# General_Overview.net
KiCad netlist of a schematic drawn in Altium Designer
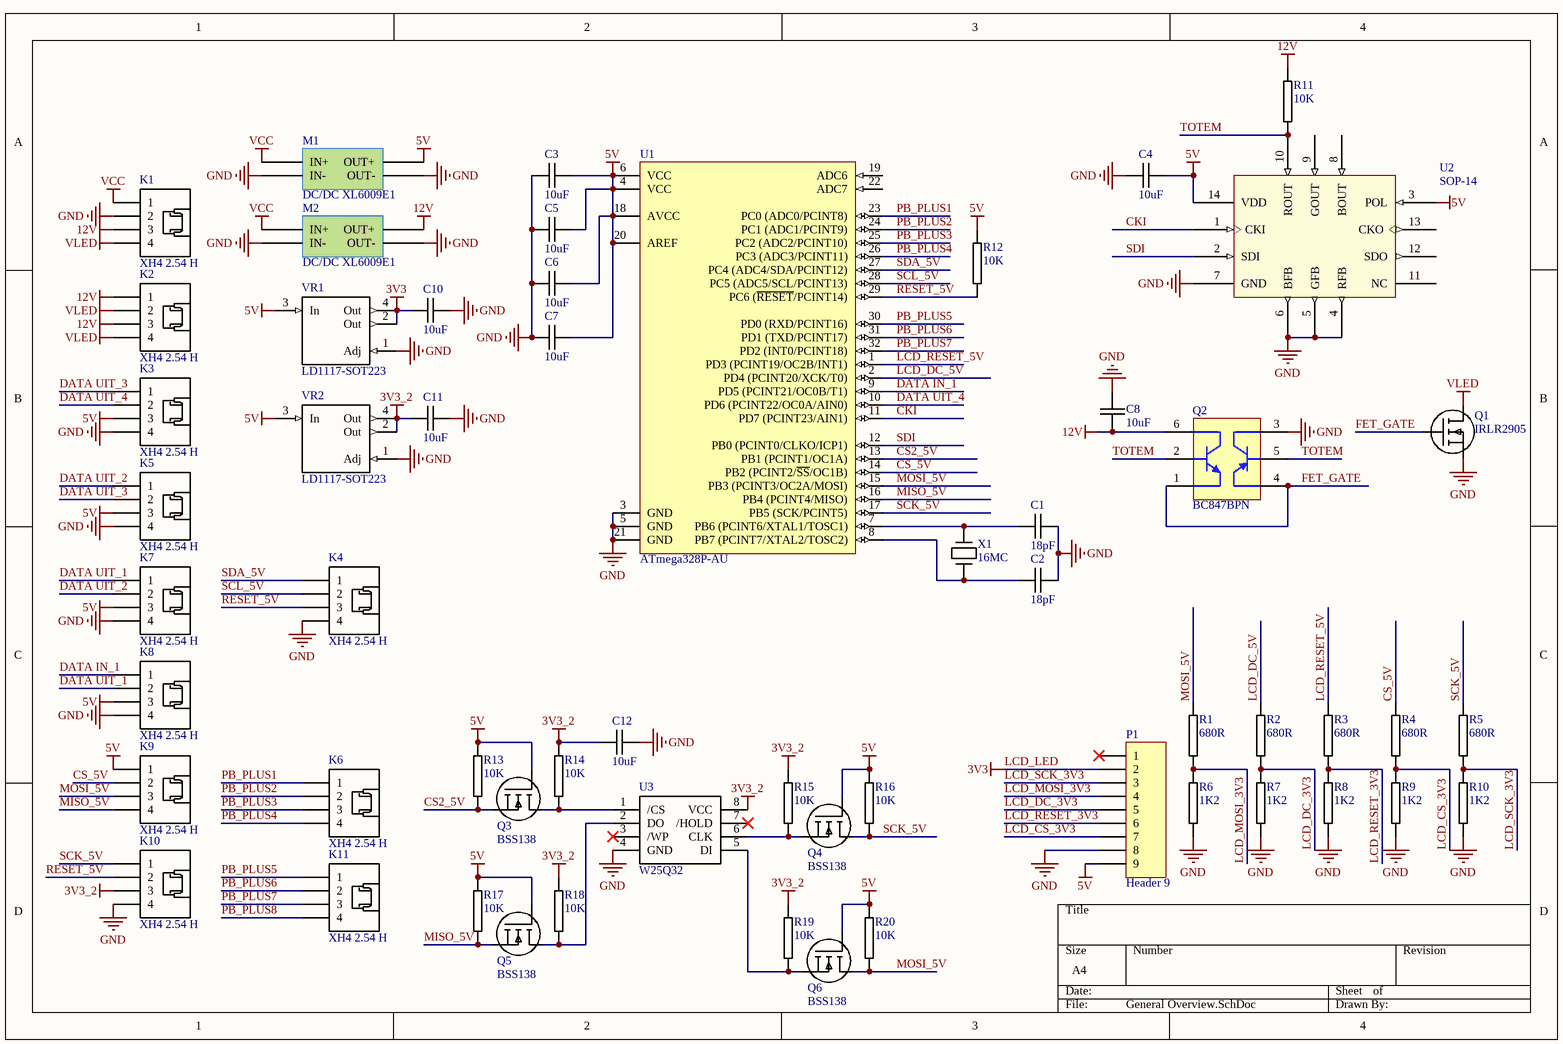
[diagram p0: General Overview.SchDoc]

(export (version "E")
  (design (tool "Eeschema 10.0.6"))
  (components
    (comp (ref "C1")
      (value "18pF")
      (footprint "0603C-GENERIC")
      (description "CAPACITOR 0603 CERAMIC")
      (libsource (lib "SMD Capacitors 0603") (part "0603C-15PF-50V-C0G-MUR"))
    )
    (comp (ref "C2")
      (value "18pF")
      (footprint "0603C-GENERIC")
      (description "CAPACITOR 0603 CERAMIC")
      (libsource (lib "SMD Capacitors 0603") (part "0603C-15PF-50V-C0G-MUR"))
    )
    (comp (ref "C3")
      (value "10uF")
      (footprint "0805C-GENERIC")
      (description "CAPACITOR 0805 CERAMIC")
      (libsource (lib "SMD Capacitors 0805") (part "0805C-10UF-25V-X5R-SAM"))
    )
    (comp (ref "C4")
      (value "10uF")
      (footprint "0805C-GENERIC")
      (description "CAPACITOR 0805 CERAMIC")
      (libsource (lib "SMD Capacitors 0805") (part "0805C-10UF-25V-X5R-SAM"))
    )
    (comp (ref "C5")
      (value "10uF")
      (footprint "0805C-GENERIC")
      (description "CAPACITOR 0805 CERAMIC")
      (libsource (lib "SMD Capacitors 0805") (part "0805C-10UF-25V-X5R-SAM"))
    )
    (comp (ref "C6")
      (value "10uF")
      (footprint "0805C-GENERIC")
      (description "CAPACITOR 0805 CERAMIC")
      (libsource (lib "SMD Capacitors 0805") (part "0805C-10UF-25V-X5R-SAM"))
    )
    (comp (ref "C7")
      (value "10uF")
      (footprint "0805C-GENERIC")
      (description "CAPACITOR 0805 CERAMIC")
      (libsource (lib "SMD Capacitors 0805") (part "0805C-10UF-25V-X5R-SAM"))
    )
    (comp (ref "C8")
      (value "10uF")
      (footprint "0805C-GENERIC")
      (description "CAPACITOR 0805 CERAMIC")
      (libsource (lib "SMD Capacitors 0805") (part "0805C-10UF-25V-X5R-SAM"))
    )
    (comp (ref "C10")
      (value "10uF")
      (footprint "0805C-GENERIC")
      (description "CAPACITOR 0805 CERAMIC")
      (libsource (lib "SMD Capacitors 0805") (part "0805C-10UF-25V-X5R-SAM"))
    )
    (comp (ref "C11")
      (value "10uF")
      (footprint "0805C-GENERIC")
      (description "CAPACITOR 0805 CERAMIC")
      (libsource (lib "SMD Capacitors 0805") (part "0805C-10UF-25V-X5R-SAM"))
    )
    (comp (ref "C12")
      (value "10uF")
      (footprint "0805C-GENERIC")
      (description "CAPACITOR 0805 CERAMIC")
      (libsource (lib "SMD Capacitors 0805") (part "0805C-10UF-25V-X5R-SAM"))
    )
    (comp (ref "K1")
      (value "XH4 2.54 H")
      (footprint "XH4 2.54 H")
      (description "4 PIN XH 2.54")
      (libsource (lib "TH Connectors") (part "XH4 2.54 H"))
    )
    (comp (ref "K2")
      (value "XH4 2.54 H")
      (footprint "XH4 2.54 H")
      (description "4 PIN XH 2.54")
      (libsource (lib "TH Connectors") (part "XH4 2.54 H"))
    )
    (comp (ref "K3")
      (value "XH4 2.54 H")
      (footprint "XH4 2.54 H")
      (description "4 PIN XH 2.54")
      (libsource (lib "TH Connectors") (part "XH4 2.54 H"))
    )
    (comp (ref "K4")
      (value "XH4 2.54 H")
      (footprint "XH4 2.54 H")
      (description "4 PIN XH 2.54")
      (libsource (lib "TH Connectors") (part "XH4 2.54 H"))
    )
    (comp (ref "K5")
      (value "XH4 2.54 H")
      (footprint "XH4 2.54 H")
      (description "4 PIN XH 2.54")
      (libsource (lib "TH Connectors") (part "XH4 2.54 H"))
    )
    (comp (ref "K6")
      (value "XH4 2.54 H")
      (footprint "XH4 2.54 H")
      (description "4 PIN XH 2.54")
      (libsource (lib "TH Connectors") (part "XH4 2.54 H"))
    )
    (comp (ref "K7")
      (value "XH4 2.54 H")
      (footprint "XH4 2.54 H")
      (description "4 PIN XH 2.54")
      (libsource (lib "TH Connectors") (part "XH4 2.54 H"))
    )
    (comp (ref "K8")
      (value "XH4 2.54 H")
      (footprint "XH4 2.54 H")
      (description "4 PIN XH 2.54")
      (libsource (lib "TH Connectors") (part "XH4 2.54 H"))
    )
    (comp (ref "K9")
      (value "XH4 2.54 H")
      (footprint "XH4 2.54 H")
      (description "4 PIN XH 2.54")
      (libsource (lib "TH Connectors") (part "XH4 2.54 H"))
    )
    (comp (ref "K10")
      (value "XH4 2.54 H")
      (footprint "XH4 2.54 H")
      (description "4 PIN XH 2.54")
      (libsource (lib "TH Connectors") (part "XH4 2.54 H"))
    )
    (comp (ref "K11")
      (value "XH4 2.54 H")
      (footprint "XH4 2.54 H")
      (description "4 PIN XH 2.54")
      (libsource (lib "TH Connectors") (part "XH4 2.54 H"))
    )
    (comp (ref "M1")
      (value "DC/DC XL6009E1")
      (footprint "DCDC XL6009E1")
      (libsource (lib "Modules") (part "DC/DC XL6009E1"))
    )
    (comp (ref "M2")
      (value "DC/DC XL6009E1")
      (footprint "DCDC XL6009E1")
      (libsource (lib "Modules") (part "DC/DC XL6009E1"))
    )
    (comp (ref "P1")
      (value "Header 9")
      (footprint "HDR1X9")
      (description "Header, 9-Pin")
      (fields (field (name "PUBLISHER") "Altium Limited"))
      (libsource (lib "Miscellaneous Connectors") (part "Header 9"))
    )
    (comp (ref "Q1")
      (value "IRLR2905")
      (footprint "TO252AA-GDS")
      (description "N CHANNEL MOSFET")
      (libsource (lib "SMD Transistors") (part "IRLR2905"))
    )
    (comp (ref "Q2")
      (value "BC847BPN")
      (footprint "SOT363_N")
      (description "NPN/PNP General-purpose Transistors")
      (fields (field (name "PUBLISHER") "Altium Limited"))
      (libsource (lib "Philips Discrete BJT - Low Power") (part "BC847BPN"))
    )
    (comp (ref "Q3")
      (value "BSS138")
      (footprint "SOT23-GDS")
      (description "N CHANNEL MOSFET")
      (fields
        (field (name "MANUFACTURER") "Infineon Technologies")
        (field (name "MANUFACTURER PART NUMBER") "BSS84P L6327")
      )
      (libsource (lib "SMD Transistors") (part "BSS138"))
    )
    (comp (ref "Q4")
      (value "BSS138")
      (footprint "SOT23-GDS")
      (description "N CHANNEL MOSFET")
      (fields
        (field (name "MANUFACTURER") "Infineon Technologies")
        (field (name "MANUFACTURER PART NUMBER") "BSS84P L6327")
      )
      (libsource (lib "SMD Transistors") (part "BSS138"))
    )
    (comp (ref "Q5")
      (value "BSS138")
      (footprint "SOT23-GDS")
      (description "N CHANNEL MOSFET")
      (fields
        (field (name "MANUFACTURER") "Infineon Technologies")
        (field (name "MANUFACTURER PART NUMBER") "BSS84P L6327")
      )
      (libsource (lib "SMD Transistors") (part "BSS138"))
    )
    (comp (ref "Q6")
      (value "BSS138")
      (footprint "SOT23-GDS")
      (description "N CHANNEL MOSFET")
      (fields
        (field (name "MANUFACTURER") "Infineon Technologies")
        (field (name "MANUFACTURER PART NUMBER") "BSS84P L6327")
      )
      (libsource (lib "SMD Transistors") (part "BSS138"))
    )
    (comp (ref "R1")
      (value "680R")
      (footprint "0805R-680")
      (description "RESISTOR 0805 1/4 WATT THIN FILM")
      (libsource (lib "SMD Resistors 0805") (part "0805R-680"))
    )
    (comp (ref "R2")
      (value "680R")
      (footprint "0805R-680")
      (description "RESISTOR 0805 1/4 WATT THIN FILM")
      (libsource (lib "SMD Resistors 0805") (part "0805R-680"))
    )
    (comp (ref "R3")
      (value "680R")
      (footprint "0805R-680")
      (description "RESISTOR 0805 1/4 WATT THIN FILM")
      (libsource (lib "SMD Resistors 0805") (part "0805R-680"))
    )
    (comp (ref "R4")
      (value "680R")
      (footprint "0805R-680")
      (description "RESISTOR 0805 1/4 WATT THIN FILM")
      (libsource (lib "SMD Resistors 0805") (part "0805R-680"))
    )
    (comp (ref "R5")
      (value "680R")
      (footprint "0805R-680")
      (description "RESISTOR 0805 1/4 WATT THIN FILM")
      (libsource (lib "SMD Resistors 0805") (part "0805R-680"))
    )
    (comp (ref "R6")
      (value "1K2")
      (footprint "0805R-1K2")
      (description "RESISTOR 0805 1/4 WATT THIN FILM")
      (libsource (lib "SMD Resistors 0805") (part "0805R-1K2"))
    )
    (comp (ref "R7")
      (value "1K2")
      (footprint "0805R-1K2")
      (description "RESISTOR 0805 1/4 WATT THIN FILM")
      (libsource (lib "SMD Resistors 0805") (part "0805R-1K2"))
    )
    (comp (ref "R8")
      (value "1K2")
      (footprint "0805R-1K2")
      (description "RESISTOR 0805 1/4 WATT THIN FILM")
      (libsource (lib "SMD Resistors 0805") (part "0805R-1K2"))
    )
    (comp (ref "R9")
      (value "1K2")
      (footprint "0805R-1K2")
      (description "RESISTOR 0805 1/4 WATT THIN FILM")
      (libsource (lib "SMD Resistors 0805") (part "0805R-1K2"))
    )
    (comp (ref "R10")
      (value "1K2")
      (footprint "0805R-1K2")
      (description "RESISTOR 0805 1/4 WATT THIN FILM")
      (libsource (lib "SMD Resistors 0805") (part "0805R-1K2"))
    )
    (comp (ref "R11")
      (value "10K")
      (footprint "0805R-10K")
      (description "RESISTOR 0805 1/4 WATT THIN FILM")
      (libsource (lib "SMD Resistors 0805") (part "0805R-10K"))
    )
    (comp (ref "R12")
      (value "10K")
      (footprint "0805R-10K")
      (description "RESISTOR 0805 1/4 WATT THIN FILM")
      (libsource (lib "SMD Resistors 0805") (part "0805R-10K"))
    )
    (comp (ref "R13")
      (value "10K")
      (footprint "0805R-10K")
      (description "RESISTOR 0805 1/4 WATT THIN FILM")
      (libsource (lib "SMD Resistors 0805") (part "0805R-10K"))
    )
    (comp (ref "R14")
      (value "10K")
      (footprint "0805R-10K")
      (description "RESISTOR 0805 1/4 WATT THIN FILM")
      (libsource (lib "SMD Resistors 0805") (part "0805R-10K"))
    )
    (comp (ref "R15")
      (value "10K")
      (footprint "0805R-10K")
      (description "RESISTOR 0805 1/4 WATT THIN FILM")
      (libsource (lib "SMD Resistors 0805") (part "0805R-10K"))
    )
    (comp (ref "R16")
      (value "10K")
      (footprint "0805R-10K")
      (description "RESISTOR 0805 1/4 WATT THIN FILM")
      (libsource (lib "SMD Resistors 0805") (part "0805R-10K"))
    )
    (comp (ref "R17")
      (value "10K")
      (footprint "0805R-10K")
      (description "RESISTOR 0805 1/4 WATT THIN FILM")
      (libsource (lib "SMD Resistors 0805") (part "0805R-10K"))
    )
    (comp (ref "R18")
      (value "10K")
      (footprint "0805R-10K")
      (description "RESISTOR 0805 1/4 WATT THIN FILM")
      (libsource (lib "SMD Resistors 0805") (part "0805R-10K"))
    )
    (comp (ref "R19")
      (value "10K")
      (footprint "0805R-10K")
      (description "RESISTOR 0805 1/4 WATT THIN FILM")
      (libsource (lib "SMD Resistors 0805") (part "0805R-10K"))
    )
    (comp (ref "R20")
      (value "10K")
      (footprint "0805R-10K")
      (description "RESISTOR 0805 1/4 WATT THIN FILM")
      (libsource (lib "SMD Resistors 0805") (part "0805R-10K"))
    )
    (comp (ref "U1")
      (value "ATmega328P-AU")
      (footprint "32A_N")
      (fields (field (name "PUBLISHER") "Altium Limited"))
      (libsource (lib "Atmel Microcontroller 8-Bit megaAVR") (part "ATmega328P-AU"))
    )
    (comp (ref "U2") (value "SOP-14") (footprint "SO14") (libsource (lib "IC-Power") (part "WS2801")))
    (comp (ref "U3") (value "W25Q32") (footprint "SO8") (libsource (lib "SPI") (part "W25Q32")))
    (comp (ref "VR1")
      (value "LD1117-SOT223")
      (footprint "SOT223")
      (libsource (lib "IC-Regulators") (part "LD1117-SOT223"))
    )
    (comp (ref "VR2")
      (value "LD1117-SOT223")
      (footprint "SOT223")
      (libsource (lib "IC-Regulators") (part "LD1117-SOT223"))
    )
    (comp (ref "X1")
      (value "16MC")
      (footprint "HC49_US TH")
      (description "16MHZ CRSYTAL HC49US")
      (libsource (lib "Crystals") (part "16MC-HC49US TH"))
    )
  )
  (nets
    (net (code "1") (name "/CKI") (class "Default")
      (node (ref "U1") (pin "11") (pinfunction "PD7_(PCINT23/AIN1)_11") (pintype "bidirectional"))
      (node (ref "U2") (pin "1") (pinfunction "CKI_1") (pintype "input"))
    )
    (net (code "2") (name "/CS2_5V") (class "Default")
      (node (ref "Q3") (pin "S") (pintype "passive"))
      (node (ref "R13") (pin "2") (pintype "passive"))
      (node (ref "U1") (pin "13") (pinfunction "PB1_(PCINT1/OC1A)_13") (pintype "bidirectional"))
    )
    (net (code "3") (name "/CS_5V") (class "Default")
      (node (ref "K9") (pin "2") (pinfunction "2_2") (pintype "passive"))
      (node (ref "R4") (pin "1") (pintype "passive"))
      (node (ref "U1") (pin "14") (pinfunction "PB2_(PCINT2/~{SS}/OC1B)_14") (pintype "bidirectional"))
    )
    (net (code "4") (name "/DATA IN_1") (class "Default")
      (node (ref "K8") (pin "1") (pinfunction "1_1") (pintype "passive"))
      (node (ref "U1") (pin "9") (pinfunction "PD5_(PCINT21/OC0B/T1)_9") (pintype "bidirectional"))
    )
    (net (code "5") (name "/DATA UIT_1") (class "Default")
      (node (ref "K7") (pin "1") (pinfunction "1_1") (pintype "passive"))
      (node (ref "K8") (pin "2") (pinfunction "2_2") (pintype "passive"))
    )
    (net (code "6") (name "/DATA UIT_2") (class "Default")
      (node (ref "K5") (pin "1") (pinfunction "1_1") (pintype "passive"))
      (node (ref "K7") (pin "2") (pinfunction "2_2") (pintype "passive"))
    )
    (net (code "7") (name "/DATA UIT_3") (class "Default")
      (node (ref "K3") (pin "1") (pinfunction "1_1") (pintype "passive"))
      (node (ref "K5") (pin "2") (pinfunction "2_2") (pintype "passive"))
    )
    (net (code "8") (name "/DATA UIT_4") (class "Default")
      (node (ref "K3") (pin "2") (pinfunction "2_2") (pintype "passive"))
      (node (ref "U1") (pin "10") (pinfunction "PD6_(PCINT22/OC0A/AIN0)_10") (pintype "bidirectional"))
    )
    (net (code "9") (name "/FET_GATE") (class "Default")
      (node (ref "Q1") (pin "G") (pintype "passive"))
      (node (ref "Q2") (pin "1") (pinfunction "E1_1") (pintype "passive"))
      (node (ref "Q2") (pin "4") (pinfunction "E2_4") (pintype "passive"))
    )
    (net (code "10") (name "/LCD_CS_3V3") (class "Default")
      (node (ref "P1") (pin "7") (pinfunction "7_7") (pintype "passive"))
      (node (ref "R4") (pin "2") (pintype "passive"))
      (node (ref "R9") (pin "1") (pintype "passive"))
    )
    (net (code "11") (name "/LCD_DC_3V3") (class "Default")
      (node (ref "P1") (pin "5") (pinfunction "5_5") (pintype "passive"))
      (node (ref "R2") (pin "2") (pintype "passive"))
      (node (ref "R7") (pin "1") (pintype "passive"))
    )
    (net (code "12") (name "/LCD_DC_5V") (class "Default")
      (node (ref "R2") (pin "1") (pintype "passive"))
      (node (ref "U1") (pin "2") (pinfunction "PD4_(PCINT20/XCK/T0)_2") (pintype "bidirectional"))
    )
    (net (code "13") (name "/LCD_MOSI_3V3") (class "Default")
      (node (ref "P1") (pin "4") (pinfunction "4_4") (pintype "passive"))
      (node (ref "R1") (pin "2") (pintype "passive"))
      (node (ref "R6") (pin "1") (pintype "passive"))
    )
    (net (code "14") (name "/LCD_RESET_3V3") (class "Default")
      (node (ref "P1") (pin "6") (pinfunction "6_6") (pintype "passive"))
      (node (ref "R3") (pin "2") (pintype "passive"))
      (node (ref "R8") (pin "1") (pintype "passive"))
    )
    (net (code "15") (name "/LCD_RESET_5V") (class "Default")
      (node (ref "R3") (pin "1") (pintype "passive"))
      (node (ref "U1") (pin "1") (pinfunction "PD3_(PCINT19/OC2B/INT1)_1") (pintype "bidirectional"))
    )
    (net (code "16") (name "/LCD_SCK_3V3") (class "Default")
      (node (ref "P1") (pin "3") (pinfunction "3_3") (pintype "passive"))
      (node (ref "R10") (pin "1") (pintype "passive"))
      (node (ref "R5") (pin "2") (pintype "passive"))
    )
    (net (code "17") (name "/MISO_5V") (class "Default")
      (node (ref "K9") (pin "4") (pinfunction "4_4") (pintype "passive"))
      (node (ref "Q5") (pin "S") (pintype "passive"))
      (node (ref "R17") (pin "2") (pintype "passive"))
      (node (ref "U1") (pin "16") (pinfunction "PB4_(PCINT4/MISO)_16") (pintype "bidirectional"))
    )
    (net (code "18") (name "/MOSI_5V") (class "Default")
      (node (ref "K9") (pin "3") (pinfunction "3_3") (pintype "passive"))
      (node (ref "Q6") (pin "D") (pintype "passive"))
      (node (ref "R1") (pin "1") (pintype "passive"))
      (node (ref "R20") (pin "2") (pintype "passive"))
      (node (ref "U1") (pin "15") (pinfunction "PB3_(PCINT3/OC2A/MOSI)_15") (pintype "bidirectional"))
    )
    (net (code "19") (name "/PB_PLUS1") (class "Default")
      (node (ref "K6") (pin "1") (pinfunction "1_1") (pintype "passive"))
      (node (ref "U1") (pin "23") (pinfunction "PC0_(ADC0/PCINT8)_23") (pintype "bidirectional"))
    )
    (net (code "20") (name "/PB_PLUS2") (class "Default")
      (node (ref "K6") (pin "2") (pinfunction "2_2") (pintype "passive"))
      (node (ref "U1") (pin "24") (pinfunction "PC1_(ADC1/PCINT9)_24") (pintype "bidirectional"))
    )
    (net (code "21") (name "/PB_PLUS3") (class "Default")
      (node (ref "K6") (pin "3") (pinfunction "3_3") (pintype "passive"))
      (node (ref "U1") (pin "25") (pinfunction "PC2_(ADC2/PCINT10)_25") (pintype "bidirectional"))
    )
    (net (code "22") (name "/PB_PLUS4") (class "Default")
      (node (ref "K6") (pin "4") (pinfunction "4_4") (pintype "passive"))
      (node (ref "U1") (pin "26") (pinfunction "PC3_(ADC3/PCINT11)_26") (pintype "bidirectional"))
    )
    (net (code "23") (name "/PB_PLUS5") (class "Default")
      (node (ref "K11") (pin "1") (pinfunction "1_1") (pintype "passive"))
      (node (ref "U1") (pin "30") (pinfunction "PD0_(RXD/PCINT16)_30") (pintype "bidirectional"))
    )
    (net (code "24") (name "/PB_PLUS6") (class "Default")
      (node (ref "K11") (pin "2") (pinfunction "2_2") (pintype "passive"))
      (node (ref "U1") (pin "31") (pinfunction "PD1_(TXD/PCINT17)_31") (pintype "bidirectional"))
    )
    (net (code "25") (name "/PB_PLUS7") (class "Default")
      (node (ref "K11") (pin "3") (pinfunction "3_3") (pintype "passive"))
      (node (ref "U1") (pin "32") (pinfunction "PD2_(INT0/PCINT18)_32") (pintype "bidirectional"))
    )
    (net (code "26") (name "/PB_PLUS8") (class "Default")
      (node (ref "K11") (pin "4") (pinfunction "4_4") (pintype "passive"))
    )
    (net (code "27") (name "/RESET_5V") (class "Default")
      (node (ref "K10") (pin "2") (pinfunction "2_2") (pintype "passive"))
      (node (ref "K4") (pin "3") (pinfunction "3_3") (pintype "passive"))
      (node (ref "R12") (pin "2") (pintype "passive"))
      (node (ref "U1") (pin "29") (pinfunction "PC6_(~{RESET}/PCINT14)_29") (pintype "bidirectional"))
    )
    (net (code "28") (name "/SCK_5V") (class "Default")
      (node (ref "K10") (pin "1") (pinfunction "1_1") (pintype "passive"))
      (node (ref "Q4") (pin "D") (pintype "passive"))
      (node (ref "R16") (pin "2") (pintype "passive"))
      (node (ref "R5") (pin "1") (pintype "passive"))
      (node (ref "U1") (pin "17") (pinfunction "PB5_(SCK/PCINT5)_17") (pintype "bidirectional"))
    )
    (net (code "29") (name "/SCL_5V") (class "Default")
      (node (ref "K4") (pin "2") (pinfunction "2_2") (pintype "passive"))
      (node (ref "U1") (pin "28") (pinfunction "PC5_(ADC5/SCL/PCINT13)_28") (pintype "bidirectional"))
    )
    (net (code "30") (name "/SDA_5V") (class "Default")
      (node (ref "K4") (pin "1") (pinfunction "1_1") (pintype "passive"))
      (node (ref "U1") (pin "27") (pinfunction "PC4_(ADC4/SDA/PCINT12)_27") (pintype "bidirectional"))
    )
    (net (code "31") (name "/SDI") (class "Default")
      (node (ref "U1") (pin "12") (pinfunction "PB0_(PCINT0/CLKO/ICP1)_12") (pintype "bidirectional"))
      (node (ref "U2") (pin "2") (pinfunction "SDI_2") (pintype "input"))
    )
    (net (code "32") (name "/TOTEM") (class "Default")
      (node (ref "Q2") (pin "2") (pinfunction "B1_2") (pintype "passive"))
      (node (ref "Q2") (pin "5") (pinfunction "B2_5") (pintype "passive"))
      (node (ref "R11") (pin "2") (pintype "passive"))
      (node (ref "U2") (pin "10") (pinfunction "ROUT_10") (pintype "input"))
    )
    (net (code "33") (name "3V3") (class "Default")
      (node (ref "C10") (pin "2") (pintype "passive"))
      (node (ref "P1") (pin "2") (pinfunction "2_2") (pintype "passive"))
      (node (ref "VR1") (pin "2") (pinfunction "Out_2") (pintype "output"))
      (node (ref "VR1") (pin "4") (pinfunction "Out_4") (pintype "output"))
    )
    (net (code "34") (name "3V3_2") (class "Default")
      (node (ref "C11") (pin "2") (pintype "passive"))
      (node (ref "C12") (pin "2") (pintype "passive"))
      (node (ref "K10") (pin "3") (pinfunction "3_3") (pintype "passive"))
      (node (ref "R14") (pin "1") (pintype "passive"))
      (node (ref "R15") (pin "1") (pintype "passive"))
      (node (ref "R18") (pin "1") (pintype "passive"))
      (node (ref "R19") (pin "1") (pintype "passive"))
      (node (ref "U3") (pin "8") (pinfunction "VCC_8") (pintype "passive"))
      (node (ref "VR2") (pin "2") (pinfunction "Out_2") (pintype "output"))
      (node (ref "VR2") (pin "4") (pinfunction "Out_4") (pintype "output"))
    )
    (net (code "35") (name "5V") (class "Default")
      (node (ref "C3") (pin "1") (pintype "passive"))
      (node (ref "C4") (pin "1") (pintype "passive"))
      (node (ref "C5") (pin "2") (pintype "passive"))
      (node (ref "C6") (pin "2") (pintype "passive"))
      (node (ref "C7") (pin "2") (pintype "passive"))
      (node (ref "K3") (pin "3") (pinfunction "3_3") (pintype "passive"))
      (node (ref "K5") (pin "3") (pinfunction "3_3") (pintype "passive"))
      (node (ref "K7") (pin "3") (pinfunction "3_3") (pintype "passive"))
      (node (ref "K8") (pin "3") (pinfunction "3_3") (pintype "passive"))
      (node (ref "K9") (pin "1") (pinfunction "1_1") (pintype "passive"))
      (node (ref "M1") (pin "OUT+") (pinfunction "OUT+_OUT+") (pintype "passive"))
      (node (ref "P1") (pin "9") (pinfunction "9_9") (pintype "passive"))
      (node (ref "Q3") (pin "G") (pintype "passive"))
      (node (ref "Q4") (pin "G") (pintype "passive"))
      (node (ref "Q5") (pin "G") (pintype "passive"))
      (node (ref "Q6") (pin "G") (pintype "passive"))
      (node (ref "R12") (pin "1") (pintype "passive"))
      (node (ref "R13") (pin "1") (pintype "passive"))
      (node (ref "R16") (pin "1") (pintype "passive"))
      (node (ref "R17") (pin "1") (pintype "passive"))
      (node (ref "R20") (pin "1") (pintype "passive"))
      (node (ref "U1") (pin "18") (pinfunction "AVCC_18") (pintype "power_in"))
      (node (ref "U1") (pin "20") (pinfunction "AREF_20") (pintype "passive"))
      (node (ref "U1") (pin "4") (pinfunction "VCC_4") (pintype "power_in"))
      (node (ref "U1") (pin "6") (pinfunction "VCC_6") (pintype "power_in"))
      (node (ref "U2") (pin "14") (pinfunction "VDD_14") (pintype "power_in"))
      (node (ref "U2") (pin "3") (pinfunction "POL_3") (pintype "input"))
      (node (ref "VR1") (pin "3") (pinfunction "In_3") (pintype "input"))
      (node (ref "VR2") (pin "3") (pinfunction "In_3") (pintype "input"))
    )
    (net (code "36") (name "12V") (class "Default")
      (node (ref "C8") (pin "2") (pintype "passive"))
      (node (ref "K1") (pin "3") (pinfunction "3_3") (pintype "passive"))
      (node (ref "K2") (pin "1") (pinfunction "1_1") (pintype "passive"))
      (node (ref "K2") (pin "3") (pinfunction "3_3") (pintype "passive"))
      (node (ref "M2") (pin "OUT+") (pinfunction "OUT+_OUT+") (pintype "passive"))
      (node (ref "Q2") (pin "6") (pinfunction "C1_6") (pintype "passive"))
      (node (ref "R11") (pin "1") (pintype "passive"))
    )
    (net (code "37") (name "GND") (class "Default")
      (node (ref "C1") (pin "2") (pintype "passive"))
      (node (ref "C10") (pin "1") (pintype "passive"))
      (node (ref "C11") (pin "1") (pintype "passive"))
      (node (ref "C12") (pin "1") (pintype "passive"))
      (node (ref "C2") (pin "2") (pintype "passive"))
      (node (ref "C3") (pin "2") (pintype "passive"))
      (node (ref "C4") (pin "2") (pintype "passive"))
      (node (ref "C5") (pin "1") (pintype "passive"))
      (node (ref "C6") (pin "1") (pintype "passive"))
      (node (ref "C7") (pin "1") (pintype "passive"))
      (node (ref "C8") (pin "1") (pintype "passive"))
      (node (ref "K1") (pin "2") (pinfunction "2_2") (pintype "passive"))
      (node (ref "K10") (pin "4") (pinfunction "4_4") (pintype "passive"))
      (node (ref "K3") (pin "4") (pinfunction "4_4") (pintype "passive"))
      (node (ref "K4") (pin "4") (pinfunction "4_4") (pintype "passive"))
      (node (ref "K5") (pin "4") (pinfunction "4_4") (pintype "passive"))
      (node (ref "K7") (pin "4") (pinfunction "4_4") (pintype "passive"))
      (node (ref "K8") (pin "4") (pinfunction "4_4") (pintype "passive"))
      (node (ref "M1") (pin "IN-") (pinfunction "IN-_IN-") (pintype "passive"))
      (node (ref "M1") (pin "OUT-") (pinfunction "OUT-_OUT-") (pintype "passive"))
      (node (ref "M2") (pin "IN-") (pinfunction "IN-_IN-") (pintype "passive"))
      (node (ref "M2") (pin "OUT-") (pinfunction "OUT-_OUT-") (pintype "passive"))
      (node (ref "P1") (pin "8") (pinfunction "8_8") (pintype "passive"))
      (node (ref "Q1") (pin "S") (pintype "passive"))
      (node (ref "Q2") (pin "3") (pinfunction "C2_3") (pintype "passive"))
      (node (ref "R10") (pin "2") (pintype "passive"))
      (node (ref "R6") (pin "2") (pintype "passive"))
      (node (ref "R7") (pin "2") (pintype "passive"))
      (node (ref "R8") (pin "2") (pintype "passive"))
      (node (ref "R9") (pin "2") (pintype "passive"))
      (node (ref "U1") (pin "21") (pinfunction "GND_21") (pintype "power_in"))
      (node (ref "U1") (pin "3") (pinfunction "GND_3") (pintype "power_in"))
      (node (ref "U1") (pin "5") (pinfunction "GND_5") (pintype "power_in"))
      (node (ref "U2") (pin "4") (pinfunction "RFB_4") (pintype "output"))
      (node (ref "U2") (pin "5") (pinfunction "GFB_5") (pintype "output"))
      (node (ref "U2") (pin "6") (pinfunction "BFB_6") (pintype "output"))
      (node (ref "U2") (pin "7") (pinfunction "GND_7") (pintype "power_in"))
      (node (ref "U3") (pin "4") (pinfunction "GND_4") (pintype "passive"))
      (node (ref "VR1") (pin "1") (pinfunction "Adj_1") (pintype "input"))
      (node (ref "VR2") (pin "1") (pinfunction "Adj_1") (pintype "input"))
    )
    (net (code "38") (name "Net-(U1-PB6_(PCINT6{slash}XTAL1{slash}TOSC1))") (class "Default")
      (node (ref "C1") (pin "1") (pintype "passive"))
      (node (ref "U1") (pin "7") (pinfunction "PB6_(PCINT6/XTAL1/TOSC1)_7") (pintype "bidirectional"))
      (node (ref "X1") (pin "1") (pintype "passive"))
    )
    (net (code "39") (name "Net-(U1-PB7_(PCINT7{slash}XTAL2{slash}TOSC2))") (class "Default")
      (node (ref "C2") (pin "1") (pintype "passive"))
      (node (ref "U1") (pin "8") (pinfunction "PB7_(PCINT7/XTAL2/TOSC2)_8") (pintype "bidirectional"))
      (node (ref "X1") (pin "2") (pintype "passive"))
    )
    (net (code "40") (name "Net-(U3-CLK)") (class "Default")
      (node (ref "Q4") (pin "S") (pintype "passive"))
      (node (ref "R15") (pin "2") (pintype "passive"))
      (node (ref "U3") (pin "6") (pinfunction "CLK_6") (pintype "passive"))
    )
    (net (code "41") (name "Net-(U3-DI)") (class "Default")
      (node (ref "Q6") (pin "S") (pintype "passive"))
      (node (ref "R19") (pin "2") (pintype "passive"))
      (node (ref "U3") (pin "5") (pinfunction "DI_5") (pintype "passive"))
    )
    (net (code "42") (name "Net-(U3-DO)") (class "Default")
      (node (ref "Q5") (pin "D") (pintype "passive"))
      (node (ref "R18") (pin "2") (pintype "passive"))
      (node (ref "U3") (pin "2") (pinfunction "DO_2") (pintype "passive"))
    )
    (net (code "43") (name "Net-(U3-{slash}CS)") (class "Default")
      (node (ref "Q3") (pin "D") (pintype "passive"))
      (node (ref "R14") (pin "2") (pintype "passive"))
      (node (ref "U3") (pin "1") (pinfunction "/CS_1") (pintype "passive"))
    )
    (net (code "44") (name "VCC") (class "Default")
      (node (ref "K1") (pin "1") (pinfunction "1_1") (pintype "passive"))
      (node (ref "M1") (pin "IN+") (pinfunction "IN+_IN+") (pintype "passive"))
      (node (ref "M2") (pin "IN+") (pinfunction "IN+_IN+") (pintype "passive"))
    )
    (net (code "45") (name "VLED") (class "Default")
      (node (ref "K1") (pin "4") (pinfunction "4_4") (pintype "passive"))
      (node (ref "K2") (pin "2") (pinfunction "2_2") (pintype "passive"))
      (node (ref "K2") (pin "4") (pinfunction "4_4") (pintype "passive"))
      (node (ref "Q1") (pin "D") (pintype "passive"))
    )
    (net (code "46") (name "unconnected-(P1-Pad1)") (class "Default")
      (node (ref "P1") (pin "1") (pinfunction "1_1") (pintype "passive+no_connect"))
    )
    (net (code "47") (name "unconnected-(U1-ADC6-Pad19)") (class "Default")
      (node (ref "U1") (pin "19") (pinfunction "ADC6_19") (pintype "input"))
    )
    (net (code "48") (name "unconnected-(U1-ADC7-Pad22)") (class "Default")
      (node (ref "U1") (pin "22") (pinfunction "ADC7_22") (pintype "input"))
    )
    (net (code "49") (name "unconnected-(U2-BOUT-Pad8)") (class "Default")
      (node (ref "U2") (pin "8") (pinfunction "BOUT_8") (pintype "input"))
    )
    (net (code "50") (name "unconnected-(U2-CKO-Pad13)") (class "Default")
      (node (ref "U2") (pin "13") (pinfunction "CKO_13") (pintype "output"))
    )
    (net (code "51") (name "unconnected-(U2-GOUT-Pad9)") (class "Default")
      (node (ref "U2") (pin "9") (pinfunction "GOUT_9") (pintype "input"))
    )
    (net (code "52") (name "unconnected-(U2-NC-Pad11)") (class "Default")
      (node (ref "U2") (pin "11") (pinfunction "NC_11") (pintype "passive"))
    )
    (net (code "53") (name "unconnected-(U2-SDO-Pad12)") (class "Default")
      (node (ref "U2") (pin "12") (pinfunction "SDO_12") (pintype "output"))
    )
    (net (code "54") (name "unconnected-(U3-{slash}HOLD-Pad7)") (class "Default")
      (node (ref "U3") (pin "7") (pinfunction "/HOLD_7") (pintype "passive+no_connect"))
    )
    (net (code "55") (name "unconnected-(U3-{slash}WP-Pad3)") (class "Default")
      (node (ref "U3") (pin "3") (pinfunction "/WP_3") (pintype "passive+no_connect"))
    )
  )
)
